# Accelerometer.net
KiCad netlist of a schematic drawn in Altium Designer
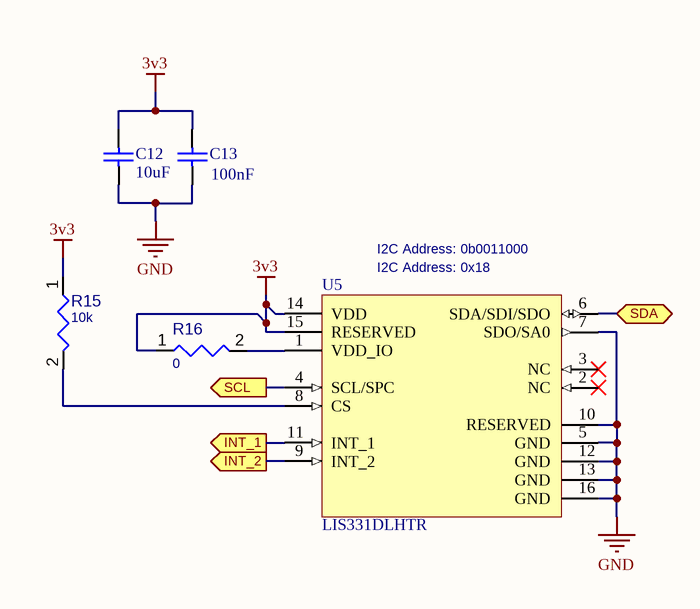
[diagram p0: Accelerometer.SchDoc]

(export (version "E")
  (design (tool "Eeschema 10.0.6"))
  (components
    (comp (ref "C12")
      (value "GRM155R60J106ME44D")
      (footprint "Capacitor_0402")
      (description "CAP CER 10UF 6.3V X5R 0402")
      (fields (field (name "CAPACITANCE") "10uF") (field (name "TOLERANCE") "20%"))
      (libsource (lib "RIT Launch Initiative") (part "CAPACITOR"))
    )
    (comp (ref "C13")
      (value "GRM155R71E104KE14D")
      (footprint "Capacitor_0402")
      (description "Chip Capacitor 100nF 0402 25V X7R")
      (fields (field (name "CAPACITANCE") "100nF"))
      (libsource (lib "RIT Launch Initiative") (part "CAPACITOR"))
    )
    (comp (ref "R15")
      (value "10k")
      (footprint "RESC0402(1005)_L")
      (description "Chip Resistor, 10 kOhms, +/-1 %, 63 mW, -55 to 125 degC, 0402")
      (fields (field (name "POWER") "63mW") (field (name "TOLERANCE") "1%"))
      (libsource (lib "RIT Launch Initiative") (part "RES-2"))
    )
    (comp (ref "R16")
      (value "0")
      (footprint "RESC0402(1005)_L")
      (description "Jumper 0402")
      (libsource (lib "RIT Launch Initiative") (part "RES-2"))
    )
    (comp (ref "U5")
      (value "LIS331DLHTR")
      (footprint "STM-LGA16-3X3X1")
      (description "LIS331DLH Series 3 Axis ±2/±4/±8 g 3.6V Digital Output Nano Accelerometer LGA-16")
      (libsource (lib "RIT Launch Initiative") (part "SEN-MOT-LIS331DL-16"))
    )
  )
  (nets
    (net (code "1") (name "/INT_1") (class "Default")
      (node (ref "U5") (pin "11") (pinfunction "INT_1_11") (pintype "input"))
    )
    (net (code "2") (name "/INT_2") (class "Default")
      (node (ref "U5") (pin "9") (pinfunction "INT_2_9") (pintype "input"))
    )
    (net (code "3") (name "/SCL") (class "Default")
      (node (ref "U5") (pin "4") (pinfunction "SCL/SPC_4") (pintype "input"))
    )
    (net (code "4") (name "/SDA") (class "Default")
      (node (ref "U5") (pin "6") (pinfunction "SDA/SDI/SDO_6") (pintype "bidirectional"))
    )
    (net (code "5") (name "3v3") (class "Default")
      (node (ref "C12") (pin "2") (pinfunction "2_2") (pintype "passive"))
      (node (ref "C13") (pin "2") (pinfunction "2_2") (pintype "passive"))
      (node (ref "R15") (pin "1") (pinfunction "1_1") (pintype "passive"))
      (node (ref "R16") (pin "1") (pinfunction "1_1") (pintype "passive"))
      (node (ref "U5") (pin "14") (pinfunction "VDD_14") (pintype "power_in"))
      (node (ref "U5") (pin "15") (pinfunction "RESERVED_15") (pintype "power_in"))
    )
    (net (code "6") (name "GND") (class "Default")
      (node (ref "C12") (pin "1") (pinfunction "1_1") (pintype "passive"))
      (node (ref "C13") (pin "1") (pinfunction "1_1") (pintype "passive"))
      (node (ref "U5") (pin "10") (pinfunction "RESERVED_10") (pintype "passive"))
      (node (ref "U5") (pin "12") (pinfunction "GND_12") (pintype "passive"))
      (node (ref "U5") (pin "13") (pinfunction "GND_13") (pintype "passive"))
      (node (ref "U5") (pin "16") (pinfunction "GND_16") (pintype "passive"))
      (node (ref "U5") (pin "5") (pinfunction "GND_5") (pintype "passive"))
      (node (ref "U5") (pin "7") (pinfunction "SDO/SA0_7") (pintype "output"))
    )
    (net (code "7") (name "Net-(U5-CS)") (class "Default")
      (node (ref "R15") (pin "2") (pinfunction "2_2") (pintype "passive"))
      (node (ref "U5") (pin "8") (pinfunction "CS_8") (pintype "input"))
    )
    (net (code "8") (name "Net-(U5-VDD_IO)") (class "Default")
      (node (ref "R16") (pin "2") (pinfunction "2_2") (pintype "passive"))
      (node (ref "U5") (pin "1") (pinfunction "VDD_IO_1") (pintype "power_in"))
    )
    (net (code "9") (name "unconnected-(U5-NC-Pad2)") (class "Default")
      (node (ref "U5") (pin "2") (pinfunction "NC_2") (pintype "input+no_connect"))
    )
    (net (code "10") (name "unconnected-(U5-NC-Pad3)") (class "Default")
      (node (ref "U5") (pin "3") (pinfunction "NC_3") (pintype "input+no_connect"))
    )
  )
)
